# Arduino_Detectors.net
KiCad netlist of a schematic drawn in EAGLE
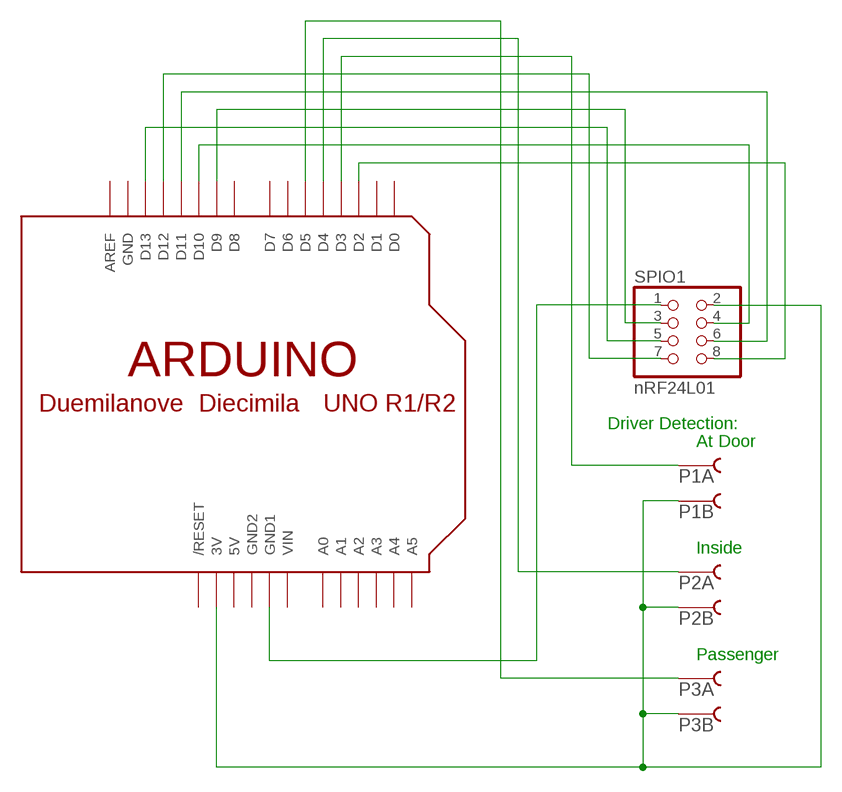
[diagram p0: schematic, sheet 1]

(export (version "E")
  (design (tool "Eeschema 10.0.6"))
  (components
    (comp (ref "P1")
      (value "ATDOOR")
      (footprint "eagle-import:30.202")
      (libsource (lib "eagle-import") (part "TBLOCK2-LA"))
    )
    (comp (ref "P2")
      (value "INSIDE")
      (footprint "eagle-import:30.202")
      (libsource (lib "eagle-import") (part "TBLOCK2-LA"))
    )
    (comp (ref "P3")
      (value "PASSENGER")
      (footprint "eagle-import:30.202")
      (libsource (lib "eagle-import") (part "TBLOCK2-LA"))
    )
    (comp (ref "SPIO1")
      (value "nRF24L01")
      (footprint "eagle-import:2X04")
      (libsource (lib "eagle-import") (part "PINHD-2X4"))
    )
    (comp (ref "U$1")
      (value "ARDUINO-BPLACE")
      (footprint "eagle-import:ARDUINO-BPLACE")
      (libsource (lib "eagle-import") (part "ARDUINO-BPLACE"))
    )
  )
  (nets
    (net (code "1") (name "/5V") (class "Default")
      (node (ref "U$1") (pin "5V") (pinfunction "5V_5V") (pintype "power_in"))
    )
    (net (code "2") (name "/GND") (class "Default")
      (node (ref "U$1") (pin "GND") (pinfunction "GND_GND") (pintype "power_in"))
    )
    (net (code "3") (name "/GND2") (class "Default")
      (node (ref "U$1") (pin "GND2") (pinfunction "GND2_GND2") (pintype "power_in"))
    )
    (net (code "4") (name "/VIN") (class "Default")
      (node (ref "U$1") (pin "VIN") (pinfunction "VIN_VIN") (pintype "power_in"))
    )
    (net (code "5") (name "Net-(P1A-P$1)") (class "Default")
      (node (ref "P1") (pin "1") (pinfunction "P$1_1") (pintype "bidirectional"))
      (node (ref "U$1") (pin "D3") (pinfunction "D3_D3") (pintype "bidirectional"))
    )
    (net (code "6") (name "Net-(P1B-P$1)") (class "Default")
      (node (ref "P1") (pin "2") (pinfunction "P$1_2") (pintype "bidirectional"))
      (node (ref "P2") (pin "2") (pinfunction "P$1_2") (pintype "bidirectional"))
      (node (ref "P3") (pin "2") (pinfunction "P$1_2") (pintype "bidirectional"))
      (node (ref "SPIO1") (pin "2") (pinfunction "2_2") (pintype "passive"))
      (node (ref "U$1") (pin "3V") (pinfunction "3V_3V") (pintype "power_in"))
    )
    (net (code "7") (name "Net-(P2A-P$1)") (class "Default")
      (node (ref "P2") (pin "1") (pinfunction "P$1_1") (pintype "bidirectional"))
      (node (ref "U$1") (pin "D4") (pinfunction "D4_D4") (pintype "bidirectional"))
    )
    (net (code "8") (name "Net-(P3A-P$1)") (class "Default")
      (node (ref "P3") (pin "1") (pinfunction "P$1_1") (pintype "bidirectional"))
      (node (ref "U$1") (pin "D5") (pinfunction "D5_D5") (pintype "bidirectional"))
    )
    (net (code "9") (name "Net-(SPIO1-Pad1)") (class "Default")
      (node (ref "SPIO1") (pin "1") (pinfunction "1_1") (pintype "passive"))
      (node (ref "U$1") (pin "GND1") (pinfunction "GND1_GND1") (pintype "power_in"))
    )
    (net (code "10") (name "Net-(SPIO1-Pad3)") (class "Default")
      (node (ref "SPIO1") (pin "3") (pinfunction "3_3") (pintype "passive"))
      (node (ref "U$1") (pin "D9") (pinfunction "D9_D9") (pintype "bidirectional"))
    )
    (net (code "11") (name "Net-(SPIO1-Pad4)") (class "Default")
      (node (ref "SPIO1") (pin "4") (pinfunction "4_4") (pintype "passive"))
      (node (ref "U$1") (pin "D10") (pinfunction "D10_D10") (pintype "bidirectional"))
    )
    (net (code "12") (name "Net-(SPIO1-Pad5)") (class "Default")
      (node (ref "SPIO1") (pin "5") (pinfunction "5_5") (pintype "passive"))
      (node (ref "U$1") (pin "D13") (pinfunction "D13_D13") (pintype "bidirectional"))
    )
    (net (code "13") (name "Net-(SPIO1-Pad6)") (class "Default")
      (node (ref "SPIO1") (pin "6") (pinfunction "6_6") (pintype "passive"))
      (node (ref "U$1") (pin "D11") (pinfunction "D11_D11") (pintype "bidirectional"))
    )
    (net (code "14") (name "Net-(SPIO1-Pad7)") (class "Default")
      (node (ref "SPIO1") (pin "7") (pinfunction "7_7") (pintype "passive"))
      (node (ref "U$1") (pin "D12") (pinfunction "D12_D12") (pintype "bidirectional"))
    )
    (net (code "15") (name "Net-(SPIO1-Pad8)") (class "Default")
      (node (ref "SPIO1") (pin "8") (pinfunction "8_8") (pintype "passive"))
      (node (ref "U$1") (pin "D2") (pinfunction "D2_D2") (pintype "bidirectional"))
    )
    (net (code "16") (name "unconnected-(U$1-PadA0)") (class "Default")
      (node (ref "U$1") (pin "A0") (pinfunction "A0_A0") (pintype "bidirectional"))
    )
    (net (code "17") (name "unconnected-(U$1-PadA1)") (class "Default")
      (node (ref "U$1") (pin "A1") (pinfunction "A1_A1") (pintype "bidirectional"))
    )
    (net (code "18") (name "unconnected-(U$1-PadA2)") (class "Default")
      (node (ref "U$1") (pin "A2") (pinfunction "A2_A2") (pintype "bidirectional"))
    )
    (net (code "19") (name "unconnected-(U$1-PadA3)") (class "Default")
      (node (ref "U$1") (pin "A3") (pinfunction "A3_A3") (pintype "bidirectional"))
    )
    (net (code "20") (name "unconnected-(U$1-PadA4)") (class "Default")
      (node (ref "U$1") (pin "A4") (pinfunction "A4_A4") (pintype "bidirectional"))
    )
    (net (code "21") (name "unconnected-(U$1-PadA5)") (class "Default")
      (node (ref "U$1") (pin "A5") (pinfunction "A5_A5") (pintype "bidirectional"))
    )
    (net (code "22") (name "unconnected-(U$1-PadAREF)") (class "Default")
      (node (ref "U$1") (pin "AREF") (pinfunction "AREF_AREF") (pintype "bidirectional"))
    )
    (net (code "23") (name "unconnected-(U$1-PadD0)") (class "Default")
      (node (ref "U$1") (pin "D0") (pinfunction "D0_D0") (pintype "bidirectional"))
    )
    (net (code "24") (name "unconnected-(U$1-PadD1)") (class "Default")
      (node (ref "U$1") (pin "D1") (pinfunction "D1_D1") (pintype "bidirectional"))
    )
    (net (code "25") (name "unconnected-(U$1-PadD6)") (class "Default")
      (node (ref "U$1") (pin "D6") (pinfunction "D6_D6") (pintype "bidirectional"))
    )
    (net (code "26") (name "unconnected-(U$1-PadD7)") (class "Default")
      (node (ref "U$1") (pin "D7") (pinfunction "D7_D7") (pintype "bidirectional"))
    )
    (net (code "27") (name "unconnected-(U$1-PadD8)") (class "Default")
      (node (ref "U$1") (pin "D8") (pinfunction "D8_D8") (pintype "bidirectional"))
    )
    (net (code "28") (name "unconnected-(U$1-{slash}RESET-PadRESET)") (class "Default")
      (node (ref "U$1") (pin "RESET") (pinfunction "/RESET_RESET") (pintype "bidirectional"))
    )
  )
)
